# RectifierPart.net
KiCad netlist of a schematic drawn in EAGLE
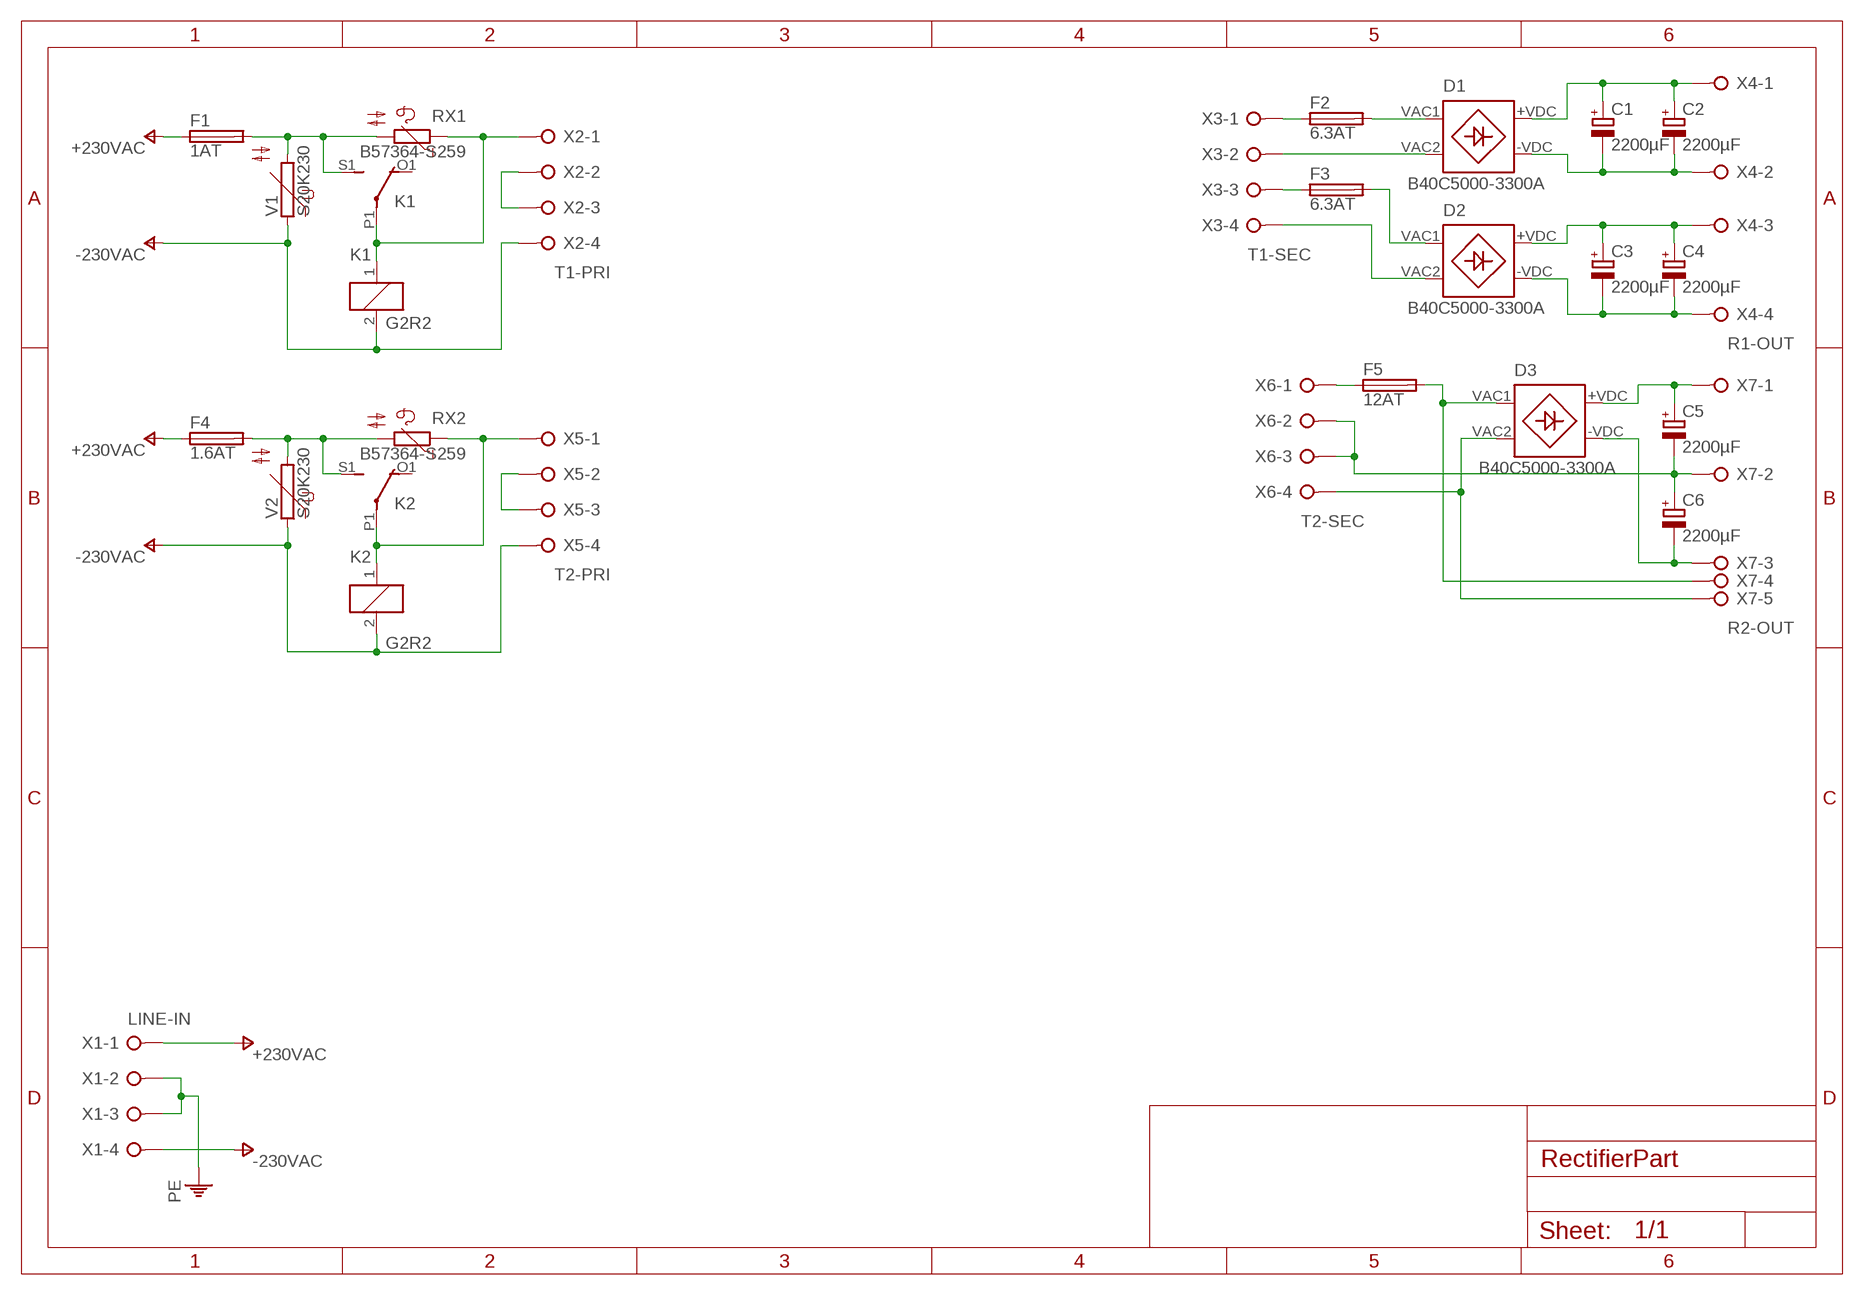
[diagram p0: schematic, sheet 1]

(export (version "E")
  (design (tool "Eeschema 10.0.6"))
  (components
    (comp (ref "C1")
      (value "2200µF")
      (footprint "eagle-import:E7,5-16")
      (libsource (lib "eagle-import") (part "CPOL-EUE7.5-16"))
    )
    (comp (ref "C2")
      (value "2200µF")
      (footprint "eagle-import:E7,5-16")
      (libsource (lib "eagle-import") (part "CPOL-EUE7.5-16"))
    )
    (comp (ref "C3")
      (value "2200µF")
      (footprint "eagle-import:E7,5-16")
      (libsource (lib "eagle-import") (part "CPOL-EUE7.5-16"))
    )
    (comp (ref "C4")
      (value "2200µF")
      (footprint "eagle-import:E7,5-16")
      (libsource (lib "eagle-import") (part "CPOL-EUE7.5-16"))
    )
    (comp (ref "C5")
      (value "2200µF")
      (footprint "eagle-import:E7,5-16")
      (libsource (lib "eagle-import") (part "CPOL-EUE7.5-16"))
    )
    (comp (ref "C6")
      (value "2200µF")
      (footprint "eagle-import:E7,5-16")
      (libsource (lib "eagle-import") (part "CPOL-EUE7.5-16"))
    )
    (comp (ref "D1")
      (value "B40C5000-3300A")
      (footprint "eagle-import:B..C")
      (libsource (lib "eagle-import") (part "B40C5000-3300A"))
    )
    (comp (ref "D2")
      (value "B40C5000-3300A")
      (footprint "eagle-import:B..C")
      (libsource (lib "eagle-import") (part "B40C5000-3300A"))
    )
    (comp (ref "D3")
      (value "B40C5000-3300A")
      (footprint "eagle-import:B..C")
      (libsource (lib "eagle-import") (part "B40C5000-3300A"))
    )
    (comp (ref "F1")
      (value "1AT")
      (footprint "eagle-import:SH22,5A")
      (fields (field (name "MPN") "0031.7701.11"))
      (libsource (lib "eagle-import") (part "SH22,5A"))
    )
    (comp (ref "F2")
      (value "6.3AT")
      (footprint "eagle-import:SH22,5A")
      (fields (field (name "MPN") "0031.7701.11"))
      (libsource (lib "eagle-import") (part "SH22,5A"))
    )
    (comp (ref "F3")
      (value "6.3AT")
      (footprint "eagle-import:SH22,5A")
      (fields (field (name "MPN") "0031.7701.11"))
      (libsource (lib "eagle-import") (part "SH22,5A"))
    )
    (comp (ref "F4")
      (value "1.6AT")
      (footprint "eagle-import:SH22,5A")
      (fields (field (name "MPN") "0031.7701.11"))
      (libsource (lib "eagle-import") (part "SH22,5A"))
    )
    (comp (ref "F5")
      (value "12AT")
      (footprint "eagle-import:SH22,5A")
      (fields (field (name "MPN") "0031.7701.11"))
      (libsource (lib "eagle-import") (part "SH22,5A"))
    )
    (comp (ref "K1")
      (value "G2R2")
      (footprint "eagle-import:G2R2")
      (fields (field (name "MF") "OMRON COMPONENTS USA") (field (name "MPN") "G2R-2-DC6"))
      (libsource (lib "eagle-import") (part "G2R2"))
    )
    (comp (ref "K2")
      (value "G2R2")
      (footprint "eagle-import:G2R2")
      (fields (field (name "MF") "OMRON COMPONENTS USA") (field (name "MPN") "G2R-2-DC6"))
      (libsource (lib "eagle-import") (part "G2R2"))
    )
    (comp (ref "RX1")
      (value "B57364-S259")
      (footprint "eagle-import:B57364S0")
      (libsource (lib "eagle-import") (part "EPCB57364-S259"))
    )
    (comp (ref "RX2")
      (value "B57364-S259")
      (footprint "eagle-import:B57364S0")
      (libsource (lib "eagle-import") (part "EPCB57364-S259"))
    )
    (comp (ref "V1")
      (value "S20K230")
      (footprint "eagle-import:S20K230")
      (libsource (lib "eagle-import") (part "S20K230"))
    )
    (comp (ref "V2")
      (value "S20K230")
      (footprint "eagle-import:S20K230")
      (libsource (lib "eagle-import") (part "S20K230"))
    )
    (comp (ref "X1")
      (value "LINE-IN")
      (footprint "eagle-import:W237-4P")
      (libsource (lib "eagle-import") (part "W237-04P"))
    )
    (comp (ref "X2")
      (value "T1-PRI")
      (footprint "eagle-import:W237-4P")
      (libsource (lib "eagle-import") (part "W237-04P"))
    )
    (comp (ref "X3")
      (value "T1-SEC")
      (footprint "eagle-import:W237-4P")
      (libsource (lib "eagle-import") (part "W237-04P"))
    )
    (comp (ref "X4")
      (value "R1-OUT")
      (footprint "eagle-import:W237-4P")
      (libsource (lib "eagle-import") (part "W237-04P"))
    )
    (comp (ref "X5")
      (value "T2-PRI")
      (footprint "eagle-import:W237-4P")
      (libsource (lib "eagle-import") (part "W237-04P"))
    )
    (comp (ref "X6")
      (value "T2-SEC")
      (footprint "eagle-import:W237-4P")
      (libsource (lib "eagle-import") (part "W237-04P"))
    )
    (comp (ref "X7")
      (value "R2-OUT")
      (footprint "eagle-import:W237-5P")
      (libsource (lib "eagle-import") (part "W237-05P"))
    )
  )
  (nets
    (net (code "1") (name "+230VAC") (class "Default")
      (node (ref "F1") (pin "1") (pinfunction "1_1") (pintype "passive"))
      (node (ref "F4") (pin "1") (pinfunction "1_1") (pintype "passive"))
      (node (ref "X1") (pin "1") (pinfunction "KL_1") (pintype "passive"))
    )
    (net (code "2") (name "-230VAC") (class "Default")
      (node (ref "K1") (pin "2") (pinfunction "2_2") (pintype "passive"))
      (node (ref "K2") (pin "2") (pinfunction "2_2") (pintype "passive"))
      (node (ref "V1") (pin "1") (pinfunction "1_1") (pintype "passive"))
      (node (ref "V2") (pin "1") (pinfunction "1_1") (pintype "passive"))
      (node (ref "X1") (pin "4") (pinfunction "KL_4") (pintype "passive"))
      (node (ref "X2") (pin "4") (pinfunction "KL_4") (pintype "passive"))
      (node (ref "X5") (pin "4") (pinfunction "KL_4") (pintype "passive"))
    )
    (net (code "3") (name "Net-(D1-PadVAC1)") (class "Default")
      (node (ref "D1") (pin "VAC1") (pinfunction "VAC1_VAC1") (pintype "input"))
      (node (ref "F2") (pin "2") (pinfunction "2_2") (pintype "passive"))
    )
    (net (code "4") (name "Net-(D2-PadVAC1)") (class "Default")
      (node (ref "D2") (pin "VAC1") (pinfunction "VAC1_VAC1") (pintype "input"))
      (node (ref "F3") (pin "2") (pinfunction "2_2") (pintype "passive"))
    )
    (net (code "5") (name "Net-(K1B-P)") (class "Default")
      (node (ref "K1") (pin "1") (pinfunction "1_1") (pintype "passive"))
      (node (ref "K1") (pin "P1") (pinfunction "P_P1") (pintype "passive"))
      (node (ref "RX1") (pin "P$1") (pinfunction "1_P$1") (pintype "passive"))
      (node (ref "X2") (pin "1") (pinfunction "KL_1") (pintype "passive"))
    )
    (net (code "6") (name "Net-(K1B-S)") (class "Default")
      (node (ref "F1") (pin "2") (pinfunction "2_2") (pintype "passive"))
      (node (ref "K1") (pin "S1") (pinfunction "S_S1") (pintype "passive"))
      (node (ref "RX1") (pin "P$2") (pinfunction "2_P$2") (pintype "passive"))
      (node (ref "V1") (pin "2") (pinfunction "2_2") (pintype "passive"))
    )
    (net (code "7") (name "Net-(K2B-P)") (class "Default")
      (node (ref "K2") (pin "1") (pinfunction "1_1") (pintype "passive"))
      (node (ref "K2") (pin "P1") (pinfunction "P_P1") (pintype "passive"))
      (node (ref "RX2") (pin "P$1") (pinfunction "1_P$1") (pintype "passive"))
      (node (ref "X5") (pin "1") (pinfunction "KL_1") (pintype "passive"))
    )
    (net (code "8") (name "Net-(K2B-S)") (class "Default")
      (node (ref "F4") (pin "2") (pinfunction "2_2") (pintype "passive"))
      (node (ref "K2") (pin "S1") (pinfunction "S_S1") (pintype "passive"))
      (node (ref "RX2") (pin "P$2") (pinfunction "2_P$2") (pintype "passive"))
      (node (ref "V2") (pin "2") (pinfunction "2_2") (pintype "passive"))
    )
    (net (code "9") (name "Net-(X2B-KL)") (class "Default")
      (node (ref "X2") (pin "2") (pinfunction "KL_2") (pintype "passive"))
      (node (ref "X2") (pin "3") (pinfunction "KL_3") (pintype "passive"))
    )
    (net (code "10") (name "Net-(X3A-KL)") (class "Default")
      (node (ref "F2") (pin "1") (pinfunction "1_1") (pintype "passive"))
      (node (ref "X3") (pin "1") (pinfunction "KL_1") (pintype "passive"))
    )
    (net (code "11") (name "Net-(X3B-KL)") (class "Default")
      (node (ref "D1") (pin "VAC2") (pinfunction "VAC2_VAC2") (pintype "input"))
      (node (ref "X3") (pin "2") (pinfunction "KL_2") (pintype "passive"))
    )
    (net (code "12") (name "Net-(X3C-KL)") (class "Default")
      (node (ref "F3") (pin "1") (pinfunction "1_1") (pintype "passive"))
      (node (ref "X3") (pin "3") (pinfunction "KL_3") (pintype "passive"))
    )
    (net (code "13") (name "Net-(X3D-KL)") (class "Default")
      (node (ref "D2") (pin "VAC2") (pinfunction "VAC2_VAC2") (pintype "input"))
      (node (ref "X3") (pin "4") (pinfunction "KL_4") (pintype "passive"))
    )
    (net (code "14") (name "Net-(X4A-KL)") (class "Default")
      (node (ref "C1") (pin "+") (pinfunction "+_+") (pintype "passive"))
      (node (ref "C2") (pin "+") (pinfunction "+_+") (pintype "passive"))
      (node (ref "D1") (pin "+VDC") (pinfunction "+VDC_+VDC") (pintype "output"))
      (node (ref "X4") (pin "1") (pinfunction "KL_1") (pintype "passive"))
    )
    (net (code "15") (name "Net-(X4B-KL)") (class "Default")
      (node (ref "C1") (pin "-") (pinfunction "-_-") (pintype "passive"))
      (node (ref "C2") (pin "-") (pinfunction "-_-") (pintype "passive"))
      (node (ref "D1") (pin "-VDC") (pinfunction "-VDC_-VDC") (pintype "output"))
      (node (ref "X4") (pin "2") (pinfunction "KL_2") (pintype "passive"))
    )
    (net (code "16") (name "Net-(X4C-KL)") (class "Default")
      (node (ref "C3") (pin "+") (pinfunction "+_+") (pintype "passive"))
      (node (ref "C4") (pin "+") (pinfunction "+_+") (pintype "passive"))
      (node (ref "D2") (pin "+VDC") (pinfunction "+VDC_+VDC") (pintype "output"))
      (node (ref "X4") (pin "3") (pinfunction "KL_3") (pintype "passive"))
    )
    (net (code "17") (name "Net-(X4D-KL)") (class "Default")
      (node (ref "C3") (pin "-") (pinfunction "-_-") (pintype "passive"))
      (node (ref "C4") (pin "-") (pinfunction "-_-") (pintype "passive"))
      (node (ref "D2") (pin "-VDC") (pinfunction "-VDC_-VDC") (pintype "output"))
      (node (ref "X4") (pin "4") (pinfunction "KL_4") (pintype "passive"))
    )
    (net (code "18") (name "Net-(X5B-KL)") (class "Default")
      (node (ref "X5") (pin "2") (pinfunction "KL_2") (pintype "passive"))
      (node (ref "X5") (pin "3") (pinfunction "KL_3") (pintype "passive"))
    )
    (net (code "19") (name "Net-(X6A-KL)") (class "Default")
      (node (ref "F5") (pin "1") (pinfunction "1_1") (pintype "passive"))
      (node (ref "X6") (pin "1") (pinfunction "KL_1") (pintype "passive"))
    )
    (net (code "20") (name "Net-(X6B-KL)") (class "Default")
      (node (ref "C5") (pin "-") (pinfunction "-_-") (pintype "passive"))
      (node (ref "C6") (pin "+") (pinfunction "+_+") (pintype "passive"))
      (node (ref "X6") (pin "2") (pinfunction "KL_2") (pintype "passive"))
      (node (ref "X6") (pin "3") (pinfunction "KL_3") (pintype "passive"))
      (node (ref "X7") (pin "2") (pinfunction "KL_2") (pintype "passive"))
    )
    (net (code "21") (name "Net-(X6D-KL)") (class "Default")
      (node (ref "D3") (pin "VAC2") (pinfunction "VAC2_VAC2") (pintype "input"))
      (node (ref "X6") (pin "4") (pinfunction "KL_4") (pintype "passive"))
      (node (ref "X7") (pin "5") (pinfunction "KL_5") (pintype "passive"))
    )
    (net (code "22") (name "Net-(X7A-KL)") (class "Default")
      (node (ref "C5") (pin "+") (pinfunction "+_+") (pintype "passive"))
      (node (ref "D3") (pin "+VDC") (pinfunction "+VDC_+VDC") (pintype "output"))
      (node (ref "X7") (pin "1") (pinfunction "KL_1") (pintype "passive"))
    )
    (net (code "23") (name "Net-(X7C-KL)") (class "Default")
      (node (ref "C6") (pin "-") (pinfunction "-_-") (pintype "passive"))
      (node (ref "D3") (pin "-VDC") (pinfunction "-VDC_-VDC") (pintype "output"))
      (node (ref "X7") (pin "3") (pinfunction "KL_3") (pintype "passive"))
    )
    (net (code "24") (name "Net-(X7D-KL)") (class "Default")
      (node (ref "D3") (pin "VAC1") (pinfunction "VAC1_VAC1") (pintype "input"))
      (node (ref "F5") (pin "2") (pinfunction "2_2") (pintype "passive"))
      (node (ref "X7") (pin "4") (pinfunction "KL_4") (pintype "passive"))
    )
    (net (code "25") (name "PE") (class "Default")
      (node (ref "X1") (pin "2") (pinfunction "KL_2") (pintype "passive"))
      (node (ref "X1") (pin "3") (pinfunction "KL_3") (pintype "passive"))
    )
    (net (code "26") (name "unconnected-(K1B-O-PadO1)") (class "Default")
      (node (ref "K1") (pin "O1") (pinfunction "O_O1") (pintype "passive"))
    )
    (net (code "27") (name "unconnected-(K2B-O-PadO1)") (class "Default")
      (node (ref "K2") (pin "O1") (pinfunction "O_O1") (pintype "passive"))
    )
  )
)
